# ESRMeterN.net
KiCad netlist of a schematic drawn in EAGLE
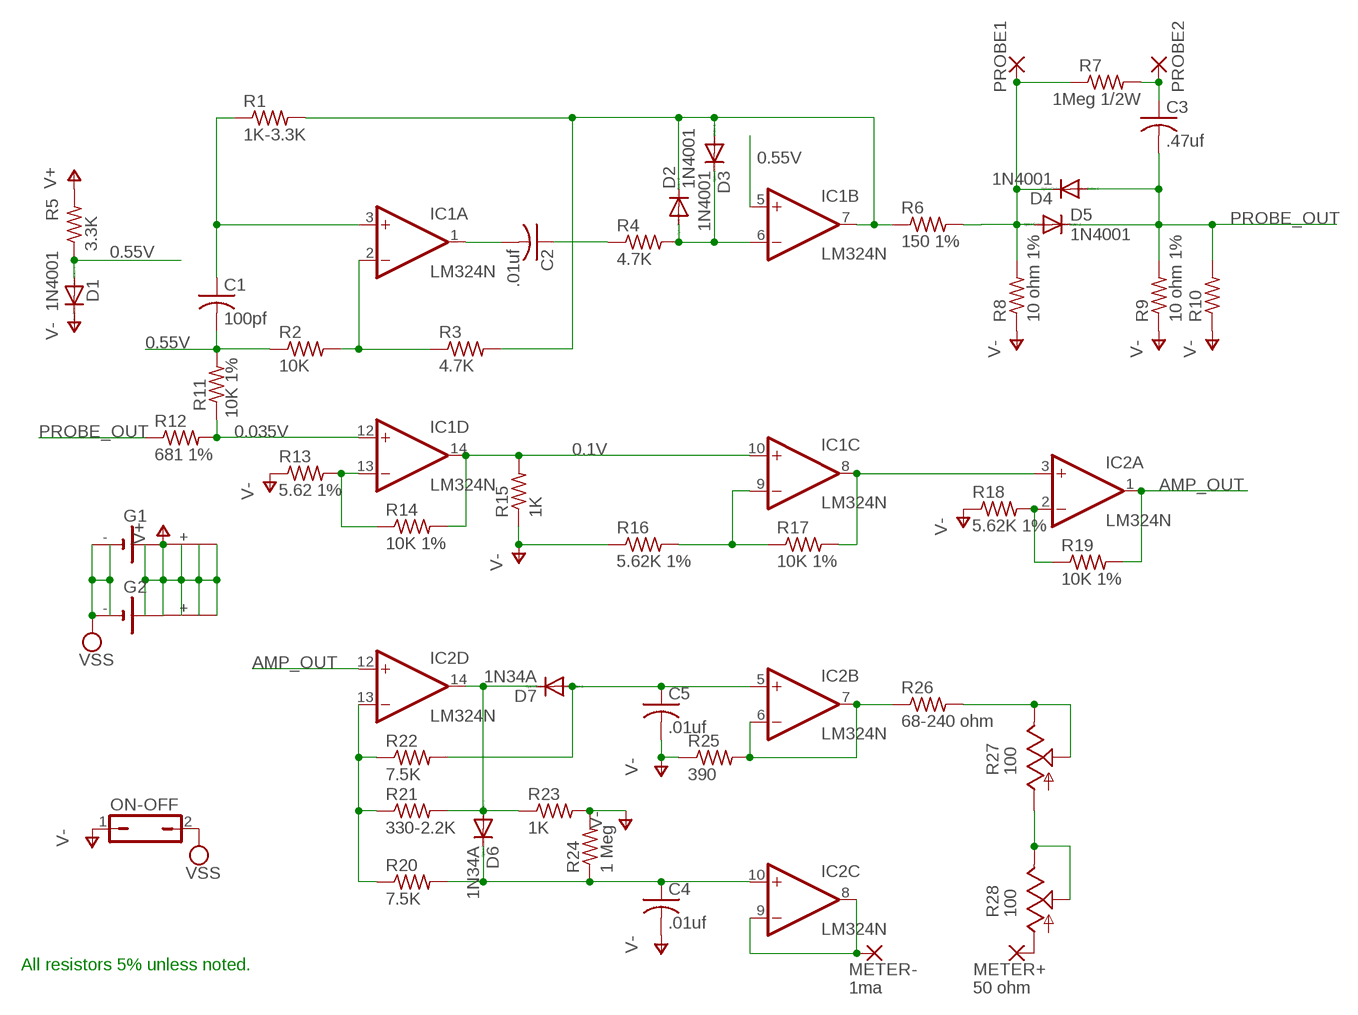
[diagram p0: schematic, sheet 1]

(export (version "E")
  (design (tool "Eeschema 10.0.6"))
  (components
    (comp (ref "C1")
      (value "100pf")
      (footprint "eagle-import:C050-025X075")
      (libsource (lib "eagle-import") (part "C-US050-025X075"))
    )
    (comp (ref "C2")
      (value ".01uf")
      (footprint "eagle-import:C050-025X075")
      (libsource (lib "eagle-import") (part "C-US050-025X075"))
    )
    (comp (ref "C3")
      (value ".47uf")
      (footprint "eagle-import:C075-032X103")
      (libsource (lib "eagle-import") (part "C-US075-032X103"))
    )
    (comp (ref "C4")
      (value ".01uf")
      (footprint "eagle-import:C050-025X075")
      (libsource (lib "eagle-import") (part "C-US050-025X075"))
    )
    (comp (ref "C5")
      (value ".01uf")
      (footprint "eagle-import:C050-025X075")
      (libsource (lib "eagle-import") (part "C-US050-025X075"))
    )
    (comp (ref "D1")
      (value "1N4001")
      (footprint "eagle-import:DO41-10")
      (libsource (lib "eagle-import") (part "1N4004"))
    )
    (comp (ref "D2")
      (value "1N4001")
      (footprint "eagle-import:DO41-10")
      (libsource (lib "eagle-import") (part "1N4004"))
    )
    (comp (ref "D3")
      (value "1N4001")
      (footprint "eagle-import:DO41-10")
      (libsource (lib "eagle-import") (part "1N4004"))
    )
    (comp (ref "D4")
      (value "1N4001")
      (footprint "eagle-import:DO41-10")
      (libsource (lib "eagle-import") (part "1N4004"))
    )
    (comp (ref "D5")
      (value "1N4001")
      (footprint "eagle-import:DO41-10")
      (libsource (lib "eagle-import") (part "1N4004"))
    )
    (comp (ref "D6")
      (value "1N34A")
      (footprint "eagle-import:DO41-10")
      (libsource (lib "eagle-import") (part "1N4004"))
    )
    (comp (ref "D7")
      (value "1N34A")
      (footprint "eagle-import:DO41-10")
      (libsource (lib "eagle-import") (part "1N4004"))
    )
    (comp (ref "G1")
      (value "B2430UNI")
      (footprint "eagle-import:B2430UNI")
      (libsource (lib "eagle-import") (part "B2430UNI"))
    )
    (comp (ref "G2")
      (value "B2430UNI")
      (footprint "eagle-import:B2430UNI")
      (libsource (lib "eagle-import") (part "B2430UNI"))
    )
    (comp (ref "IC1")
      (value "LM324N")
      (footprint "eagle-import:DIL14")
      (libsource (lib "eagle-import") (part "LM324N"))
    )
    (comp (ref "IC2")
      (value "LM324N")
      (footprint "eagle-import:DIL14")
      (libsource (lib "eagle-import") (part "LM324N"))
    )
    (comp (ref "METER+")
      (value "50 ohm")
      (footprint "eagle-import:2,15_1,0")
      (libsource (lib "eagle-import") (part "2,15/1,0"))
    )
    (comp (ref "METER-")
      (value "1ma")
      (footprint "eagle-import:2,15_1,0")
      (libsource (lib "eagle-import") (part "2,15/1,0"))
    )
    (comp (ref "ON-OFF")
      (value "JP1Q")
      (footprint "eagle-import:JP1")
      (libsource (lib "eagle-import") (part "JP1Q"))
    )
    (comp (ref "PROBE1")
      (value "2,15/1,0")
      (footprint "eagle-import:2,15_1,0")
      (libsource (lib "eagle-import") (part "2,15/1,0"))
    )
    (comp (ref "PROBE2")
      (value "2,15/1,0")
      (footprint "eagle-import:2,15_1,0")
      (libsource (lib "eagle-import") (part "2,15/1,0"))
    )
    (comp (ref "R1")
      (value "1K-3.3K")
      (footprint "eagle-import:0207_10")
      (libsource (lib "eagle-import") (part "R-US_0207/10"))
    )
    (comp (ref "R2")
      (value "10K")
      (footprint "eagle-import:0207_10")
      (libsource (lib "eagle-import") (part "R-US_0207/10"))
    )
    (comp (ref "R3")
      (value "4.7K")
      (footprint "eagle-import:0207_10")
      (libsource (lib "eagle-import") (part "R-US_0207/10"))
    )
    (comp (ref "R4")
      (value "4.7K")
      (footprint "eagle-import:0207_10")
      (libsource (lib "eagle-import") (part "R-US_0207/10"))
    )
    (comp (ref "R5")
      (value "3.3K")
      (footprint "eagle-import:0207_10")
      (libsource (lib "eagle-import") (part "R-US_0207/10"))
    )
    (comp (ref "R6")
      (value "150 1%")
      (footprint "eagle-import:0207_10")
      (libsource (lib "eagle-import") (part "R-US_0207/10"))
    )
    (comp (ref "R7")
      (value "1Meg 1/2W")
      (footprint "eagle-import:0207_12")
      (libsource (lib "eagle-import") (part "R-US_0207/12"))
    )
    (comp (ref "R8")
      (value "10 ohm 1%")
      (footprint "eagle-import:0207_10")
      (libsource (lib "eagle-import") (part "R-US_0207/10"))
    )
    (comp (ref "R9")
      (value "10 ohm 1%")
      (footprint "eagle-import:0207_10")
      (libsource (lib "eagle-import") (part "R-US_0207/10"))
    )
    (comp (ref "R10")
      (value "R-US_0207/10")
      (footprint "eagle-import:0207_10")
      (libsource (lib "eagle-import") (part "R-US_0207/10"))
    )
    (comp (ref "R11")
      (value "10K 1%")
      (footprint "eagle-import:0207_10")
      (libsource (lib "eagle-import") (part "R-US_0207/10"))
    )
    (comp (ref "R12")
      (value "681 1%")
      (footprint "eagle-import:0207_10")
      (libsource (lib "eagle-import") (part "R-US_0207/10"))
    )
    (comp (ref "R13")
      (value "5.62 1%")
      (footprint "eagle-import:0207_10")
      (libsource (lib "eagle-import") (part "R-US_0207/10"))
    )
    (comp (ref "R14")
      (value "10K 1%")
      (footprint "eagle-import:0207_10")
      (libsource (lib "eagle-import") (part "R-US_0207/10"))
    )
    (comp (ref "R15")
      (value "1K")
      (footprint "eagle-import:0207_10")
      (libsource (lib "eagle-import") (part "R-US_0207/10"))
    )
    (comp (ref "R16")
      (value "5.62K 1%")
      (footprint "eagle-import:0207_10")
      (libsource (lib "eagle-import") (part "R-US_0207/10"))
    )
    (comp (ref "R17")
      (value "10K 1%")
      (footprint "eagle-import:0207_10")
      (libsource (lib "eagle-import") (part "R-US_0207/10"))
    )
    (comp (ref "R18")
      (value "5.62K 1%")
      (footprint "eagle-import:0207_10")
      (libsource (lib "eagle-import") (part "R-US_0207/10"))
    )
    (comp (ref "R19")
      (value "10K 1%")
      (footprint "eagle-import:0207_10")
      (libsource (lib "eagle-import") (part "R-US_0207/10"))
    )
    (comp (ref "R20")
      (value "7.5K")
      (footprint "eagle-import:0207_10")
      (libsource (lib "eagle-import") (part "R-US_0207/10"))
    )
    (comp (ref "R21")
      (value "330-2.2K")
      (footprint "eagle-import:0207_10")
      (libsource (lib "eagle-import") (part "R-US_0207/10"))
    )
    (comp (ref "R22")
      (value "7.5K")
      (footprint "eagle-import:0207_10")
      (libsource (lib "eagle-import") (part "R-US_0207/10"))
    )
    (comp (ref "R23")
      (value "1K")
      (footprint "eagle-import:0207_10")
      (libsource (lib "eagle-import") (part "R-US_0207/10"))
    )
    (comp (ref "R24")
      (value "1 Meg")
      (footprint "eagle-import:0207_12")
      (libsource (lib "eagle-import") (part "R-US_0207/12"))
    )
    (comp (ref "R25")
      (value "390")
      (footprint "eagle-import:0207_10")
      (libsource (lib "eagle-import") (part "R-US_0207/10"))
    )
    (comp (ref "R26")
      (value "68-240 ohm")
      (footprint "eagle-import:0207_10")
      (libsource (lib "eagle-import") (part "R-US_0207/10"))
    )
    (comp (ref "R27")
      (value "100")
      (footprint "eagle-import:B64W")
      (libsource (lib "eagle-import") (part "TRIM_US-B64W"))
    )
    (comp (ref "R28")
      (value "100")
      (footprint "eagle-import:B64W")
      (libsource (lib "eagle-import") (part "TRIM_US-B64W"))
    )
  )
  (nets
    (net (code "1") (name "/0.1V") (class "Default")
      (node (ref "IC1") (pin "10") (pinfunction "+IN_10") (pintype "input"))
      (node (ref "IC1") (pin "14") (pinfunction "OUT_14") (pintype "output"))
      (node (ref "R14") (pin "2") (pinfunction "2_2") (pintype "passive"))
      (node (ref "R15") (pin "2") (pinfunction "2_2") (pintype "passive"))
    )
    (net (code "2") (name "/0.035V") (class "Default")
      (node (ref "IC1") (pin "12") (pinfunction "+IN_12") (pintype "input"))
      (node (ref "R11") (pin "1") (pinfunction "1_1") (pintype "passive"))
      (node (ref "R12") (pin "2") (pinfunction "2_2") (pintype "passive"))
    )
    (net (code "3") (name "/0.55V") (class "Default")
      (node (ref "C1") (pin "2") (pinfunction "2_2") (pintype "passive"))
      (node (ref "D1") (pin "A") (pinfunction "A_A") (pintype "passive"))
      (node (ref "IC1") (pin "5") (pinfunction "+IN_5") (pintype "input"))
      (node (ref "R11") (pin "2") (pinfunction "2_2") (pintype "passive"))
      (node (ref "R2") (pin "1") (pinfunction "1_1") (pintype "passive"))
      (node (ref "R5") (pin "1") (pinfunction "1_1") (pintype "passive"))
    )
    (net (code "4") (name "/AMP_OUT") (class "Default")
      (node (ref "IC2") (pin "1") (pinfunction "OUT_1") (pintype "output"))
      (node (ref "IC2") (pin "12") (pinfunction "+IN_12") (pintype "input"))
      (node (ref "R19") (pin "2") (pinfunction "2_2") (pintype "passive"))
    )
    (net (code "5") (name "/PROBE_OUT") (class "Default")
      (node (ref "C3") (pin "2") (pinfunction "2_2") (pintype "passive"))
      (node (ref "D4") (pin "A") (pinfunction "A_A") (pintype "passive"))
      (node (ref "D5") (pin "C") (pinfunction "C_C") (pintype "passive"))
      (node (ref "R10") (pin "2") (pinfunction "2_2") (pintype "passive"))
      (node (ref "R12") (pin "1") (pinfunction "1_1") (pintype "passive"))
      (node (ref "R9") (pin "2") (pinfunction "2_2") (pintype "passive"))
    )
    (net (code "6") (name "Net-(C2-Pad1)") (class "Default")
      (node (ref "C2") (pin "1") (pinfunction "1_1") (pintype "passive"))
      (node (ref "R4") (pin "1") (pinfunction "1_1") (pintype "passive"))
    )
    (net (code "7") (name "Net-(IC1A-+IN)") (class "Default")
      (node (ref "C1") (pin "1") (pinfunction "1_1") (pintype "passive"))
      (node (ref "IC1") (pin "3") (pinfunction "+IN_3") (pintype "input"))
      (node (ref "R1") (pin "1") (pinfunction "1_1") (pintype "passive"))
    )
    (net (code "8") (name "Net-(IC1A--IN)") (class "Default")
      (node (ref "IC1") (pin "2") (pinfunction "-IN_2") (pintype "input"))
      (node (ref "R2") (pin "2") (pinfunction "2_2") (pintype "passive"))
      (node (ref "R3") (pin "1") (pinfunction "1_1") (pintype "passive"))
    )
    (net (code "9") (name "Net-(IC1A-OUT)") (class "Default")
      (node (ref "C2") (pin "2") (pinfunction "2_2") (pintype "passive"))
      (node (ref "IC1") (pin "1") (pinfunction "OUT_1") (pintype "output"))
    )
    (net (code "10") (name "Net-(IC1B--IN)") (class "Default")
      (node (ref "D2") (pin "A") (pinfunction "A_A") (pintype "passive"))
      (node (ref "D3") (pin "C") (pinfunction "C_C") (pintype "passive"))
      (node (ref "IC1") (pin "6") (pinfunction "-IN_6") (pintype "input"))
      (node (ref "R4") (pin "2") (pinfunction "2_2") (pintype "passive"))
    )
    (net (code "11") (name "Net-(IC1B-OUT)") (class "Default")
      (node (ref "D2") (pin "C") (pinfunction "C_C") (pintype "passive"))
      (node (ref "D3") (pin "A") (pinfunction "A_A") (pintype "passive"))
      (node (ref "IC1") (pin "7") (pinfunction "OUT_7") (pintype "output"))
      (node (ref "R1") (pin "2") (pinfunction "2_2") (pintype "passive"))
      (node (ref "R3") (pin "2") (pinfunction "2_2") (pintype "passive"))
      (node (ref "R6") (pin "1") (pinfunction "1_1") (pintype "passive"))
    )
    (net (code "12") (name "Net-(IC1C--IN)") (class "Default")
      (node (ref "IC1") (pin "9") (pinfunction "-IN_9") (pintype "input"))
      (node (ref "R16") (pin "2") (pinfunction "2_2") (pintype "passive"))
      (node (ref "R17") (pin "1") (pinfunction "1_1") (pintype "passive"))
    )
    (net (code "13") (name "Net-(IC1C-OUT)") (class "Default")
      (node (ref "IC1") (pin "8") (pinfunction "OUT_8") (pintype "output"))
      (node (ref "IC2") (pin "3") (pinfunction "+IN_3") (pintype "input"))
      (node (ref "R17") (pin "2") (pinfunction "2_2") (pintype "passive"))
    )
    (net (code "14") (name "Net-(IC1D--IN)") (class "Default")
      (node (ref "IC1") (pin "13") (pinfunction "-IN_13") (pintype "input"))
      (node (ref "R13") (pin "2") (pinfunction "2_2") (pintype "passive"))
      (node (ref "R14") (pin "1") (pinfunction "1_1") (pintype "passive"))
    )
    (net (code "15") (name "Net-(IC2A--IN)") (class "Default")
      (node (ref "IC2") (pin "2") (pinfunction "-IN_2") (pintype "input"))
      (node (ref "R18") (pin "2") (pinfunction "2_2") (pintype "passive"))
      (node (ref "R19") (pin "1") (pinfunction "1_1") (pintype "passive"))
    )
    (net (code "16") (name "Net-(IC2B-+IN)") (class "Default")
      (node (ref "C5") (pin "1") (pinfunction "1_1") (pintype "passive"))
      (node (ref "D7") (pin "A") (pinfunction "A_A") (pintype "passive"))
      (node (ref "IC2") (pin "5") (pinfunction "+IN_5") (pintype "input"))
      (node (ref "R22") (pin "2") (pinfunction "2_2") (pintype "passive"))
    )
    (net (code "17") (name "Net-(IC2B--IN)") (class "Default")
      (node (ref "IC2") (pin "6") (pinfunction "-IN_6") (pintype "input"))
      (node (ref "IC2") (pin "7") (pinfunction "OUT_7") (pintype "output"))
      (node (ref "R25") (pin "2") (pinfunction "2_2") (pintype "passive"))
      (node (ref "R26") (pin "1") (pinfunction "1_1") (pintype "passive"))
    )
    (net (code "18") (name "Net-(IC2C-+IN)") (class "Default")
      (node (ref "C4") (pin "1") (pinfunction "1_1") (pintype "passive"))
      (node (ref "D6") (pin "C") (pinfunction "C_C") (pintype "passive"))
      (node (ref "IC2") (pin "10") (pinfunction "+IN_10") (pintype "input"))
      (node (ref "R20") (pin "2") (pinfunction "2_2") (pintype "passive"))
      (node (ref "R24") (pin "1") (pinfunction "1_1") (pintype "passive"))
    )
    (net (code "19") (name "Net-(IC2C--IN)") (class "Default")
      (node (ref "IC2") (pin "8") (pinfunction "OUT_8") (pintype "output"))
      (node (ref "IC2") (pin "9") (pinfunction "-IN_9") (pintype "input"))
      (node (ref "METER-") (pin "1") (pinfunction "P_1") (pintype "passive"))
    )
    (net (code "20") (name "Net-(IC2D--IN)") (class "Default")
      (node (ref "IC2") (pin "13") (pinfunction "-IN_13") (pintype "input"))
      (node (ref "R20") (pin "1") (pinfunction "1_1") (pintype "passive"))
      (node (ref "R21") (pin "1") (pinfunction "1_1") (pintype "passive"))
      (node (ref "R22") (pin "1") (pinfunction "1_1") (pintype "passive"))
    )
    (net (code "21") (name "Net-(IC2D-OUT)") (class "Default")
      (node (ref "D6") (pin "A") (pinfunction "A_A") (pintype "passive"))
      (node (ref "D7") (pin "C") (pinfunction "C_C") (pintype "passive"))
      (node (ref "IC2") (pin "14") (pinfunction "OUT_14") (pintype "output"))
      (node (ref "R21") (pin "2") (pinfunction "2_2") (pintype "passive"))
      (node (ref "R23") (pin "1") (pinfunction "1_1") (pintype "passive"))
    )
    (net (code "22") (name "Net-(METER+-P)") (class "Default")
      (node (ref "METER+") (pin "1") (pinfunction "P_1") (pintype "passive"))
      (node (ref "R28") (pin "A") (pinfunction "A_A") (pintype "passive"))
    )
    (net (code "23") (name "Net-(PROBE1-P)") (class "Default")
      (node (ref "D4") (pin "C") (pinfunction "C_C") (pintype "passive"))
      (node (ref "D5") (pin "A") (pinfunction "A_A") (pintype "passive"))
      (node (ref "PROBE1") (pin "1") (pinfunction "P_1") (pintype "passive"))
      (node (ref "R6") (pin "2") (pinfunction "2_2") (pintype "passive"))
      (node (ref "R7") (pin "1") (pinfunction "1_1") (pintype "passive"))
      (node (ref "R8") (pin "2") (pinfunction "2_2") (pintype "passive"))
    )
    (net (code "24") (name "Net-(PROBE2-P)") (class "Default")
      (node (ref "C3") (pin "1") (pinfunction "1_1") (pintype "passive"))
      (node (ref "PROBE2") (pin "1") (pinfunction "P_1") (pintype "passive"))
      (node (ref "R7") (pin "2") (pinfunction "2_2") (pintype "passive"))
    )
    (net (code "25") (name "Net-(R26-Pad2)") (class "Default")
      (node (ref "R26") (pin "2") (pinfunction "2_2") (pintype "passive"))
      (node (ref "R27") (pin "E") (pinfunction "E_E") (pintype "passive"))
      (node (ref "R27") (pin "S") (pinfunction "S_S") (pintype "passive"))
    )
    (net (code "26") (name "Net-(R27-PadA)") (class "Default")
      (node (ref "R27") (pin "A") (pinfunction "A_A") (pintype "passive"))
      (node (ref "R28") (pin "E") (pinfunction "E_E") (pintype "passive"))
      (node (ref "R28") (pin "S") (pinfunction "S_S") (pintype "passive"))
    )
    (net (code "27") (name "V+") (class "Default")
      (node (ref "G1") (pin "+") (pinfunction "+_+") (pintype "passive"))
      (node (ref "G1") (pin "+@1") (pinfunction "+_+@1") (pintype "passive"))
      (node (ref "G1") (pin "+@2") (pinfunction "+_+@2") (pintype "passive"))
      (node (ref "G1") (pin "+@3") (pinfunction "+_+@3") (pintype "passive"))
      (node (ref "G1") (pin "+@4") (pinfunction "+_+@4") (pintype "passive"))
      (node (ref "G2") (pin "+") (pinfunction "+_+") (pintype "passive"))
      (node (ref "G2") (pin "+@1") (pinfunction "+_+@1") (pintype "passive"))
      (node (ref "G2") (pin "+@2") (pinfunction "+_+@2") (pintype "passive"))
      (node (ref "G2") (pin "+@3") (pinfunction "+_+@3") (pintype "passive"))
      (node (ref "G2") (pin "+@4") (pinfunction "+_+@4") (pintype "passive"))
      (node (ref "R5") (pin "2") (pinfunction "2_2") (pintype "passive"))
    )
    (net (code "28") (name "V-") (class "Default")
      (node (ref "C4") (pin "2") (pinfunction "2_2") (pintype "passive"))
      (node (ref "C5") (pin "2") (pinfunction "2_2") (pintype "passive"))
      (node (ref "D1") (pin "C") (pinfunction "C_C") (pintype "passive"))
      (node (ref "ON-OFF") (pin "1") (pinfunction "1_1") (pintype "passive"))
      (node (ref "R10") (pin "1") (pinfunction "1_1") (pintype "passive"))
      (node (ref "R13") (pin "1") (pinfunction "1_1") (pintype "passive"))
      (node (ref "R15") (pin "1") (pinfunction "1_1") (pintype "passive"))
      (node (ref "R16") (pin "1") (pinfunction "1_1") (pintype "passive"))
      (node (ref "R18") (pin "1") (pinfunction "1_1") (pintype "passive"))
      (node (ref "R23") (pin "2") (pinfunction "2_2") (pintype "passive"))
      (node (ref "R24") (pin "2") (pinfunction "2_2") (pintype "passive"))
      (node (ref "R25") (pin "1") (pinfunction "1_1") (pintype "passive"))
      (node (ref "R8") (pin "1") (pinfunction "1_1") (pintype "passive"))
      (node (ref "R9") (pin "1") (pinfunction "1_1") (pintype "passive"))
    )
    (net (code "29") (name "VSS") (class "Default")
      (node (ref "G1") (pin "-") (pinfunction "-_-") (pintype "passive"))
      (node (ref "G1") (pin "-@1") (pinfunction "-_-@1") (pintype "passive"))
      (node (ref "G2") (pin "-") (pinfunction "-_-") (pintype "passive"))
      (node (ref "G2") (pin "-@1") (pinfunction "-_-@1") (pintype "passive"))
      (node (ref "ON-OFF") (pin "2") (pinfunction "2_2") (pintype "passive"))
    )
  )
)
